# PROC099A_XDS110_Interface_1A.net
KiCad netlist of a schematic drawn in Altium Designer
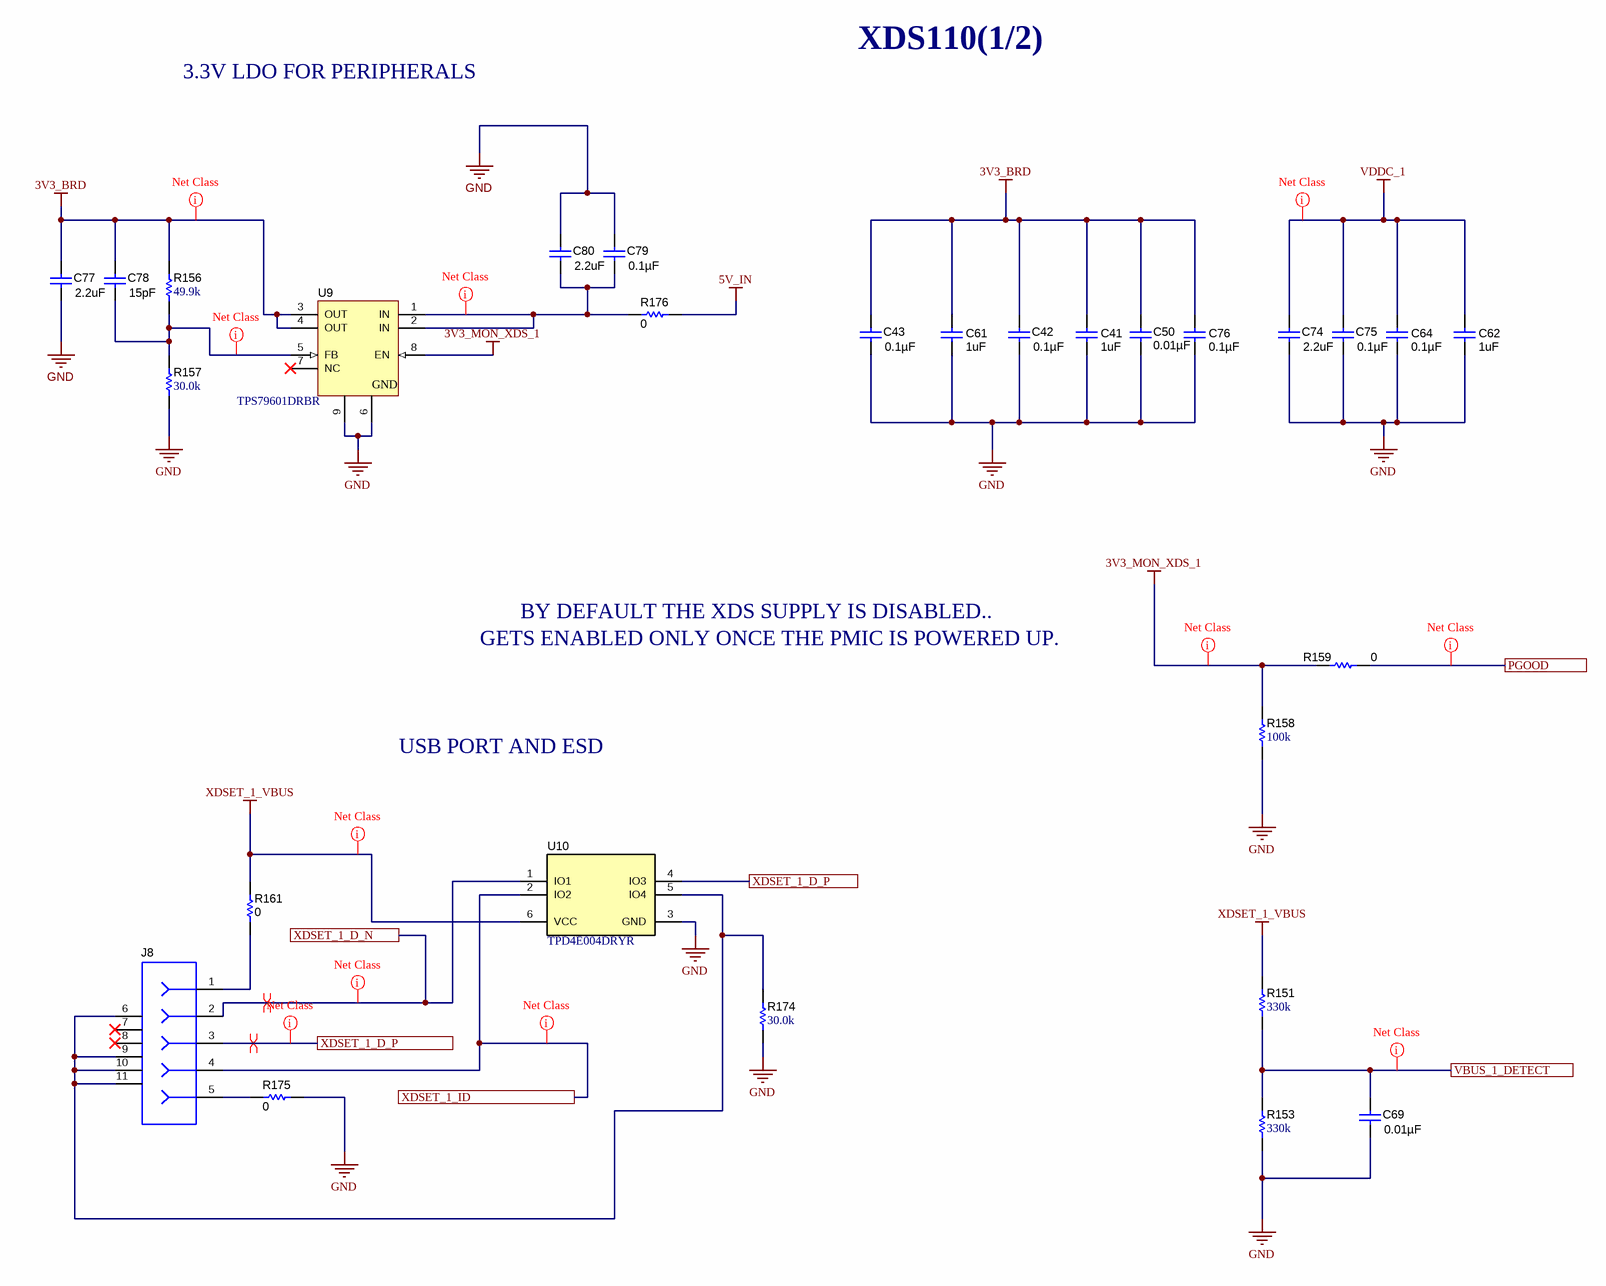
[diagram p0: PROC099A_XDS110 Interface_1A.SchDoc]

(export (version "E")
  (design (tool "Eeschema 10.0.6"))
  (components
    (comp (ref "C41")
      (value "GCM155C71A105KE38D")
      (footprint "0402_070")
      (description "CAP, CERM, 1 uF, 10 V, +/- 10%, X7S, AEC-Q200 Grade 1, 0402")
      (fields
        (field (name "MANUFACTURER") "MuRata")
        (field (name "VALUEDISPLAYED") "1uF")
        (field (name "PUBLISHER") "Texas Instruments")
      )
      (libsource (lib "Altium Vault - TI") (part "Capacitor"))
    )
    (comp (ref "C42")
      (value "C0402C104K8RACTU")
      (footprint "0402L")
      (description "CAP, CERM, 0.1 µF, 10 V,+/- 10%, X7R, 0402")
      (fields (field (name "MANUFACTURER") "Kemet") (field (name "VALUEDISPLAYED") "0.1µF"))
      (libsource (lib "Altium Vault - TI") (part "Capacitor"))
    )
    (comp (ref "C43")
      (value "C0402C104K8RACTU")
      (footprint "0402L")
      (description "CAP, CERM, 0.1 µF, 10 V,+/- 10%, X7R, 0402")
      (fields (field (name "MANUFACTURER") "Kemet") (field (name "VALUEDISPLAYED") "0.1µF"))
      (libsource (lib "Altium Vault - TI") (part "Capacitor"))
    )
    (comp (ref "C50")
      (value "C0402C103K4RACTU")
      (footprint "0402S")
      (description "CAP, CERM, 0.01 µF, 16 V,+/- 10%, X7R, 0402")
      (fields (field (name "MANUFACTURER") "Kemet") (field (name "VALUEDISPLAYED") "0.01µF"))
      (libsource (lib "Altium Vault - TI") (part "Capacitor"))
    )
    (comp (ref "C61")
      (value "GCM155C71A105KE38D")
      (footprint "0402_070")
      (description "CAP, CERM, 1 uF, 10 V, +/- 10%, X7S, AEC-Q200 Grade 1, 0402")
      (fields
        (field (name "MANUFACTURER") "MuRata")
        (field (name "VALUEDISPLAYED") "1uF")
        (field (name "PUBLISHER") "Texas Instruments")
      )
      (libsource (lib "Altium Vault - TI") (part "Capacitor"))
    )
    (comp (ref "C62")
      (value "GCM155C71A105KE38D")
      (footprint "0402_070")
      (description "CAP, CERM, 1 uF, 10 V, +/- 10%, X7S, AEC-Q200 Grade 1, 0402")
      (fields
        (field (name "MANUFACTURER") "MuRata")
        (field (name "VALUEDISPLAYED") "1uF")
        (field (name "PUBLISHER") "Texas Instruments")
      )
      (libsource (lib "Altium Vault - TI") (part "Capacitor"))
    )
    (comp (ref "C64")
      (value "C0402C104K8RACTU")
      (footprint "0402L")
      (description "CAP, CERM, 0.1 µF, 10 V,+/- 10%, X7R, 0402")
      (fields (field (name "MANUFACTURER") "Kemet") (field (name "VALUEDISPLAYED") "0.1µF"))
      (libsource (lib "Altium Vault - TI") (part "Capacitor"))
    )
    (comp (ref "C69")
      (value "C0402C103K4RACTU")
      (footprint "0402L")
      (description "CAP, CERM, 0.01 µF, 16 V,+/- 10%, X7R, 0402")
      (fields (field (name "MANUFACTURER") "Kemet") (field (name "VALUEDISPLAYED") "0.01µF"))
      (libsource (lib "Altium Vault - TI") (part "Capacitor"))
    )
    (comp (ref "C74")
      (value "C1005X7S1A225K050BC")
      (footprint "0402_065L")
      (description "CAP, CERM, 2.2 uF, 10 V, +/- 10%, X7S, 0402")
      (fields
        (field (name "MANUFACTURER") "TDK")
        (field (name "VALUEDISPLAYED") "2.2uF")
        (field (name "PUBLISHER") "Texas Instruments")
      )
      (libsource (lib "Altium Vault - TI") (part "CMP-0006302-2"))
    )
    (comp (ref "C75")
      (value "C0402C104K8RACTU")
      (footprint "0402L")
      (description "CAP, CERM, 0.1 µF, 10 V,+/- 10%, X7R, 0402")
      (fields (field (name "MANUFACTURER") "Kemet") (field (name "VALUEDISPLAYED") "0.1µF"))
      (libsource (lib "Altium Vault - TI") (part "Capacitor"))
    )
    (comp (ref "C76")
      (value "C0402C104K8RACTU")
      (footprint "0402L")
      (description "CAP, CERM, 0.1 µF, 10 V,+/- 10%, X7R, 0402")
      (fields (field (name "MANUFACTURER") "Kemet") (field (name "VALUEDISPLAYED") "0.1µF"))
      (libsource (lib "Altium Vault - TI") (part "Capacitor"))
    )
    (comp (ref "C77")
      (value "C1005X7S1A225K050BC")
      (footprint "0402_065L")
      (description "CAP, CERM, 2.2 uF, 10 V, +/- 10%, X7S, 0402")
      (fields
        (field (name "MANUFACTURER") "TDK")
        (field (name "VALUEDISPLAYED") "2.2uF")
        (field (name "PUBLISHER") "Texas Instruments")
      )
      (libsource (lib "Altium Vault - TI") (part "CMP-0006302-2"))
    )
    (comp (ref "C78")
      (value "04025A150FAT2A")
      (footprint "0402L")
      (description "CAP, CERM, 15 pF, 50 V,+/- 1%, C0G/NP0, 0402")
      (fields (field (name "MANUFACTURER") "AVX") (field (name "VALUEDISPLAYED") "15pF"))
      (libsource (lib "Altium Vault - TI") (part "Capacitor"))
    )
    (comp (ref "C79")
      (value "C0402C104K8RACTU")
      (footprint "0402L")
      (description "CAP, CERM, 0.1 µF, 10 V,+/- 10%, X7R, 0402")
      (fields (field (name "MANUFACTURER") "Kemet") (field (name "VALUEDISPLAYED") "0.1µF"))
      (libsource (lib "Altium Vault - TI") (part "Capacitor"))
    )
    (comp (ref "C80")
      (value "C1005X7S1A225K050BC")
      (footprint "0402_065L")
      (description "CAP, CERM, 2.2 uF, 10 V, +/- 10%, X7S, 0402")
      (fields
        (field (name "MANUFACTURER") "TDK")
        (field (name "VALUEDISPLAYED") "2.2uF")
        (field (name "PUBLISHER") "Texas Instruments")
      )
      (libsource (lib "Altium Vault - TI") (part "CMP-0006302-2"))
    )
    (comp (ref "J8")
      (value "105017-0001")
      (footprint "CONN_105017-0001")
      (description "Connector, Receptacle, Micro-USB Type B, R/A, Bottom Mount SMT")
      (fields (field (name "MANUFACTURER") "Molex") (field (name "PUBLISHER") "Texas Instruments"))
      (libsource (lib "Altium Vault - TI") (part "CONN_105017-0001"))
    )
    (comp (ref "R151")
      (value "CRCW0402330KFKED")
      (footprint "0402L")
      (description "RES, 330 k, 1%, 0.063 W, AEC-Q200 Grade 0, 0402")
      (fields (field (name "MANUFACTURER") "Vishay-Dale") (field (name "VALUEDISPLAYED") "330k"))
      (libsource (lib "Altium Vault - TI") (part "Resistor"))
    )
    (comp (ref "R153")
      (value "CRCW0402330KFKED")
      (footprint "0402L")
      (description "RES, 330 k, 1%, 0.063 W, AEC-Q200 Grade 0, 0402")
      (fields (field (name "MANUFACTURER") "Vishay-Dale") (field (name "VALUEDISPLAYED") "330k"))
      (libsource (lib "Altium Vault - TI") (part "Resistor"))
    )
    (comp (ref "R156")
      (value "CRCW040249K9FKED")
      (footprint "0402L")
      (description "RES, 49.9 k, 1%, 0.063 W, AEC-Q200 Grade 0, 0402")
      (fields (field (name "MANUFACTURER") "Vishay-Dale") (field (name "VALUEDISPLAYED") "49.9k"))
      (libsource (lib "Altium Vault - TI") (part "Resistor"))
    )
    (comp (ref "R157")
      (value "CRCW040230K0FKED")
      (footprint "0402L")
      (description "RES, 30.0 k, 1%, 0.063 W, AEC-Q200 Grade 0, 0402")
      (fields (field (name "MANUFACTURER") "Vishay-Dale") (field (name "VALUEDISPLAYED") "30.0k"))
      (libsource (lib "Altium Vault - TI") (part "Resistor"))
    )
    (comp (ref "R158")
      (value "CRCW0402100KFKED")
      (footprint "0402L")
      (description "RES, 100 k, 1%, 0.063 W, AEC-Q200 Grade 0, 0402")
      (fields (field (name "MANUFACTURER") "Vishay-Dale") (field (name "VALUEDISPLAYED") "100k"))
      (libsource (lib "Altium Vault - TI") (part "Resistor"))
    )
    (comp (ref "R159")
      (value "ERJ-2GE0R00X")
      (footprint "0402L")
      (description "RES, 0, 5%, 0.063 W, 0402")
      (fields
        (field (name "MANUFACTURER") "Panasonic")
        (field (name "VALUEDISPLAYED") "0")
        (field (name "PUBLISHER") "Texas Instruments")
      )
      (libsource (lib "Altium Vault - TI") (part "Resistor"))
    )
    (comp (ref "R161")
      (value "MCT06030Z0000ZP500")
      (footprint "0603")
      (description "RES, 0, 5%, 0.125 W, 0603")
      (fields
        (field (name "MANUFACTURER") "Vishay/Beyschlag")
        (field (name "VALUEDISPLAYED") "0")
        (field (name "PUBLISHER") "Texas Instruments")
      )
      (libsource (lib "Altium Vault - TI") (part "Resistor"))
    )
    (comp (ref "R174")
      (value "CRCW040230K0FKED")
      (footprint "0402L")
      (description "RES, 30.0 k, 1%, 0.063 W, AEC-Q200 Grade 0, 0402")
      (fields (field (name "MANUFACTURER") "Vishay-Dale") (field (name "VALUEDISPLAYED") "30.0k"))
      (libsource (lib "Altium Vault - TI") (part "Resistor"))
    )
    (comp (ref "R175")
      (value "MCT06030Z0000ZP500")
      (footprint "0603")
      (description "RES, 0, 5%, 0.125 W, 0603")
      (fields
        (field (name "MANUFACTURER") "Vishay/Beyschlag")
        (field (name "VALUEDISPLAYED") "0")
        (field (name "PUBLISHER") "Texas Instruments")
      )
      (libsource (lib "Altium Vault - TI") (part "Resistor"))
    )
    (comp (ref "R176")
      (value "MCT06030Z0000ZP500")
      (footprint "0603")
      (description "RES, 0, 5%, 0.125 W, 0603")
      (fields
        (field (name "MANUFACTURER") "Vishay/Beyschlag")
        (field (name "VALUEDISPLAYED") "0")
        (field (name "PUBLISHER") "Texas Instruments")
      )
      (libsource (lib "Altium Vault - TI") (part "Resistor"))
    )
    (comp (ref "U9")
      (value "TPS79601DRBR")
      (footprint "DRB0008B")
      (fields (field (name "MANUFACTURER") "Texas Instruments") (field (name "PARTNUMBER") "TPS79601DRBR"))
      (libsource (lib "Altium Vault - TI") (part "CMP-0036402-3"))
    )
    (comp (ref "U10")
      (value "TPD4E004DRYR")
      (footprint "DRY0006A")
      (fields (field (name "MANUFACTURER") "Texas Instruments") (field (name "PARTNUMBER") "TPD4E004DRYR"))
      (libsource (lib "Altium Vault - TI") (part "CMP-0043115-2"))
    )
  )
  (nets
    (net (code "1") (name "/PGOOD") (class "Default")
      (node (ref "R159") (pin "1") (pinfunction "1_1") (pintype "passive"))
    )
    (net (code "2") (name "/VBUS_1_DETECT") (class "Default")
      (node (ref "C69") (pin "2") (pinfunction "2_2") (pintype "passive"))
      (node (ref "R151") (pin "1") (pinfunction "1_1") (pintype "passive"))
      (node (ref "R153") (pin "2") (pinfunction "2_2") (pintype "passive"))
    )
    (net (code "3") (name "/XDSET_1_D_N") (class "Default")
      (node (ref "J8") (pin "2") (pintype "passive"))
      (node (ref "U10") (pin "1") (pinfunction "IO1_1") (pintype "passive"))
    )
    (net (code "4") (name "/XDSET_1_D_P") (class "Default")
      (node (ref "J8") (pin "3") (pintype "passive"))
      (node (ref "U10") (pin "4") (pinfunction "IO3_4") (pintype "passive"))
    )
    (net (code "5") (name "/XDSET_1_ID") (class "Default")
      (node (ref "J8") (pin "4") (pintype "passive"))
      (node (ref "U10") (pin "2") (pinfunction "IO2_2") (pintype "passive"))
    )
    (net (code "6") (name "3V3_BRD") (class "Default")
      (node (ref "C41") (pin "1") (pinfunction "1_1") (pintype "passive"))
      (node (ref "C42") (pin "2") (pinfunction "2_2") (pintype "passive"))
      (node (ref "C43") (pin "2") (pinfunction "2_2") (pintype "passive"))
      (node (ref "C50") (pin "1") (pinfunction "1_1") (pintype "passive"))
      (node (ref "C61") (pin "1") (pinfunction "1_1") (pintype "passive"))
      (node (ref "C76") (pin "2") (pinfunction "2_2") (pintype "passive"))
      (node (ref "C77") (pin "2") (pinfunction "2_2") (pintype "passive"))
      (node (ref "C78") (pin "2") (pinfunction "2_2") (pintype "passive"))
      (node (ref "R156") (pin "2") (pinfunction "2_2") (pintype "passive"))
      (node (ref "U9") (pin "3") (pinfunction "OUT_3") (pintype "power_in"))
      (node (ref "U9") (pin "4") (pinfunction "OUT_4") (pintype "power_in"))
    )
    (net (code "7") (name "3V3_MON_XDS_1") (class "Default")
      (node (ref "R158") (pin "2") (pinfunction "2_2") (pintype "passive"))
      (node (ref "R159") (pin "2") (pinfunction "2_2") (pintype "passive"))
      (node (ref "U9") (pin "8") (pinfunction "EN_8") (pintype "input"))
    )
    (net (code "8") (name "5V_IN") (class "Default")
      (node (ref "R176") (pin "2") (pinfunction "2_2") (pintype "passive"))
    )
    (net (code "9") (name "GND") (class "Default")
      (node (ref "C41") (pin "2") (pinfunction "2_2") (pintype "passive"))
      (node (ref "C42") (pin "1") (pinfunction "1_1") (pintype "passive"))
      (node (ref "C43") (pin "1") (pinfunction "1_1") (pintype "passive"))
      (node (ref "C50") (pin "2") (pinfunction "2_2") (pintype "passive"))
      (node (ref "C61") (pin "2") (pinfunction "2_2") (pintype "passive"))
      (node (ref "C62") (pin "2") (pinfunction "2_2") (pintype "passive"))
      (node (ref "C64") (pin "1") (pinfunction "1_1") (pintype "passive"))
      (node (ref "C69") (pin "1") (pinfunction "1_1") (pintype "passive"))
      (node (ref "C74") (pin "1") (pinfunction "1_1") (pintype "passive"))
      (node (ref "C75") (pin "1") (pinfunction "1_1") (pintype "passive"))
      (node (ref "C76") (pin "1") (pinfunction "1_1") (pintype "passive"))
      (node (ref "C77") (pin "1") (pinfunction "1_1") (pintype "passive"))
      (node (ref "C79") (pin "1") (pinfunction "1_1") (pintype "passive"))
      (node (ref "C80") (pin "1") (pinfunction "1_1") (pintype "passive"))
      (node (ref "R153") (pin "1") (pinfunction "1_1") (pintype "passive"))
      (node (ref "R157") (pin "1") (pinfunction "1_1") (pintype "passive"))
      (node (ref "R158") (pin "1") (pinfunction "1_1") (pintype "passive"))
      (node (ref "R174") (pin "1") (pinfunction "1_1") (pintype "passive"))
      (node (ref "R175") (pin "1") (pinfunction "1_1") (pintype "passive"))
      (node (ref "U10") (pin "3") (pinfunction "GND_3") (pintype "power_in"))
      (node (ref "U9") (pin "6") (pinfunction "GND_6") (pintype "power_in"))
      (node (ref "U9") (pin "9") (pinfunction "GND_9") (pintype "power_in"))
    )
    (net (code "10") (name "Net-(C79-Pad2)") (class "Default")
      (node (ref "C79") (pin "2") (pinfunction "2_2") (pintype "passive"))
      (node (ref "C80") (pin "2") (pinfunction "2_2") (pintype "passive"))
      (node (ref "R176") (pin "1") (pinfunction "1_1") (pintype "passive"))
      (node (ref "U9") (pin "1") (pinfunction "IN_1") (pintype "power_in"))
      (node (ref "U9") (pin "2") (pinfunction "IN_2") (pintype "power_in"))
    )
    (net (code "11") (name "Net-(J8-Pad1)") (class "Default")
      (node (ref "J8") (pin "1") (pintype "passive"))
      (node (ref "R161") (pin "1") (pinfunction "1_1") (pintype "passive"))
    )
    (net (code "12") (name "Net-(J8-Pad5)") (class "Default")
      (node (ref "J8") (pin "5") (pintype "passive"))
      (node (ref "R175") (pin "2") (pinfunction "2_2") (pintype "passive"))
    )
    (net (code "13") (name "Net-(U9-FB)") (class "Default")
      (node (ref "C78") (pin "1") (pinfunction "1_1") (pintype "passive"))
      (node (ref "R156") (pin "1") (pinfunction "1_1") (pintype "passive"))
      (node (ref "R157") (pin "2") (pinfunction "2_2") (pintype "passive"))
      (node (ref "U9") (pin "5") (pinfunction "FB_5") (pintype "input"))
    )
    (net (code "14") (name "Net-(U10-IO4)") (class "Default")
      (node (ref "J8") (pin "10") (pintype "passive"))
      (node (ref "J8") (pin "11") (pintype "passive"))
      (node (ref "J8") (pin "6") (pintype "passive"))
      (node (ref "J8") (pin "9") (pintype "passive"))
      (node (ref "R174") (pin "2") (pinfunction "2_2") (pintype "passive"))
      (node (ref "U10") (pin "5") (pinfunction "IO4_5") (pintype "passive"))
    )
    (net (code "15") (name "VDDC_1") (class "Default")
      (node (ref "C62") (pin "1") (pinfunction "1_1") (pintype "passive"))
      (node (ref "C64") (pin "2") (pinfunction "2_2") (pintype "passive"))
      (node (ref "C74") (pin "2") (pinfunction "2_2") (pintype "passive"))
      (node (ref "C75") (pin "2") (pinfunction "2_2") (pintype "passive"))
    )
    (net (code "16") (name "XDSET_1_VBUS") (class "Default")
      (node (ref "R151") (pin "2") (pinfunction "2_2") (pintype "passive"))
      (node (ref "R161") (pin "2") (pinfunction "2_2") (pintype "passive"))
      (node (ref "U10") (pin "6") (pinfunction "VCC_6") (pintype "power_in"))
    )
    (net (code "17") (name "unconnected-(J8-Pad7)") (class "Default")
      (node (ref "J8") (pin "7") (pintype "passive+no_connect"))
    )
    (net (code "18") (name "unconnected-(J8-Pad8)") (class "Default")
      (node (ref "J8") (pin "8") (pintype "passive+no_connect"))
    )
    (net (code "19") (name "unconnected-(U9-NC-Pad7)") (class "Default")
      (node (ref "U9") (pin "7") (pinfunction "NC_7") (pintype "passive+no_connect"))
    )
  )
)
